# Power-line.net
KiCad netlist of a schematic drawn in Altium Designer
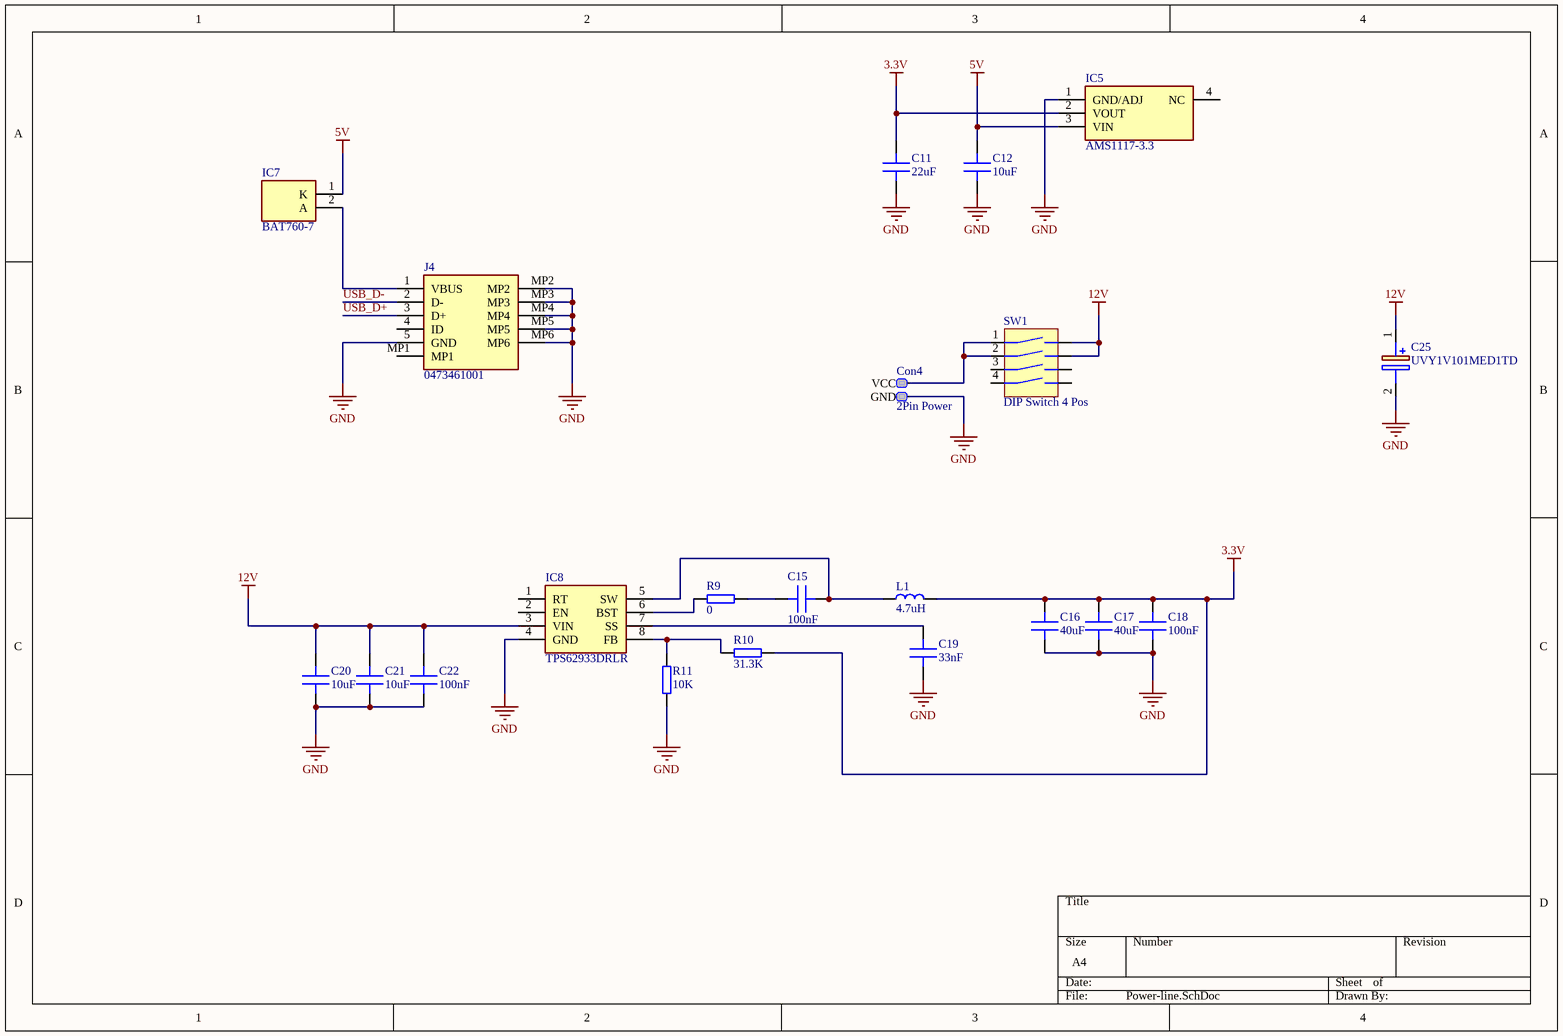
[diagram p0: Power-line.SchDoc]

(export (version "E")
  (design (tool "Eeschema 10.0.6"))
  (components
    (comp (ref "C11")
      (value "22uF")
      (footprint "C 0805")
      (description "MLCC Capacitor")
      (libsource (lib "Components") (part "Capacitor"))
    )
    (comp (ref "C12")
      (value "10uF")
      (footprint "C 0805")
      (description "MLCC Capacitor")
      (libsource (lib "Components") (part "Capacitor"))
    )
    (comp (ref "C15")
      (value "100nF")
      (footprint "C 0402")
      (description "MLCC Capacitor")
      (libsource (lib "Components") (part "Capacitor"))
    )
    (comp (ref "C16")
      (value "40uF")
      (footprint "C 1206")
      (description "MLCC Capacitor")
      (libsource (lib "Components") (part "Capacitor"))
    )
    (comp (ref "C17")
      (value "40uF")
      (footprint "C 1206")
      (description "MLCC Capacitor")
      (libsource (lib "Components") (part "Capacitor"))
    )
    (comp (ref "C18")
      (value "100nF")
      (footprint "C 0603")
      (description "MLCC Capacitor")
      (libsource (lib "Components") (part "Capacitor"))
    )
    (comp (ref "C19")
      (value "33nF")
      (footprint "C 0402")
      (description "MLCC Capacitor")
      (libsource (lib "Components") (part "Capacitor"))
    )
    (comp (ref "C20")
      (value "10uF")
      (footprint "C 1206")
      (description "MLCC Capacitor")
      (libsource (lib "Components") (part "Capacitor"))
    )
    (comp (ref "C21")
      (value "10uF")
      (footprint "C 1206")
      (description "MLCC Capacitor")
      (libsource (lib "Components") (part "Capacitor"))
    )
    (comp (ref "C22")
      (value "100nF")
      (footprint "C 0603")
      (description "MLCC Capacitor")
      (libsource (lib "Components") (part "Capacitor"))
    )
    (comp (ref "C25")
      (value "UVY1V101MED1TD")
      (footprint "SamacSys:CAPPRD250W50D655H1250")
      (description "Capacitor Polarised")
      (libsource (lib "lf_esp_sch_lib") (part "UVY1V101MED1TD"))
    )
    (comp (ref "Con4")
      (value "2Pin Power")
      (footprint "B2B-ZR-SM4A-TF")
      (libsource (lib "Connectors") (part "2Pin Power"))
    )
    (comp (ref "IC5")
      (value "AMS1117-3.3")
      (footprint "SamacSys:SOT229P700X180-4N")
      (description "Integrated Circuit")
      (libsource (lib "lf_esp_sch_lib") (part "AMS1117-3.3"))
    )
    (comp (ref "IC7")
      (value "BAT760-7")
      (footprint "SamacSys:SOD2513X120N")
      (description "Integrated Circuit")
      (libsource (lib "lf_esp_sch_lib") (part "BAT760-7"))
    )
    (comp (ref "IC8")
      (value "TPS62933DRLR")
      (footprint "SamacSys:SOTFL50P160X60-8N")
      (description "Integrated Circuit")
      (fields (field (name "MOUSER PART NUMBER") "595-TPS62933DRLR"))
      (libsource (lib "*") (part "TPS62933DRLR"))
    )
    (comp (ref "J4")
      (value "0473461001")
      (footprint "SamacSys:0473461001")
      (description "Connector")
      (libsource (lib "lf_esp_sch_lib") (part "0473461001"))
    )
    (comp (ref "L1")
      (value "4.7uH")
      (footprint "HPI0630")
      (description "General pourpouse inductor")
      (libsource (lib "Components") (part "Inductor"))
    )
    (comp (ref "R9")
      (value "0")
      (footprint "R 0402")
      (description "General pourpouse resistor")
      (libsource (lib "Components") (part "Resistor"))
    )
    (comp (ref "R10")
      (value "31.3K")
      (footprint "R 0402")
      (description "General pourpouse resistor")
      (libsource (lib "Components") (part "Resistor"))
    )
    (comp (ref "R11")
      (value "10K")
      (footprint "R 0402")
      (description "General pourpouse resistor")
      (libsource (lib "Components") (part "Resistor"))
    )
    (comp (ref "SW1")
      (value "DIP Switch 4 Pos")
      (footprint "DIP Switch 4 pos 2.54mm")
      (libsource (lib "Switches") (part "DIP Switch 4 Pos"))
    )
  )
  (nets
    (net (code "1") (name "/USB_D+") (class "Default")
      (node (ref "J4") (pin "3") (pinfunction "D+_3") (pintype "passive"))
    )
    (net (code "2") (name "/USB_D-") (class "Default")
      (node (ref "J4") (pin "2") (pinfunction "D-_2") (pintype "passive"))
    )
    (net (code "3") (name "3.3V") (class "Default")
      (node (ref "C11") (pin "1") (pinfunction "1_1") (pintype "passive"))
      (node (ref "C16") (pin "1") (pinfunction "1_1") (pintype "passive"))
      (node (ref "C17") (pin "1") (pinfunction "1_1") (pintype "passive"))
      (node (ref "C18") (pin "1") (pinfunction "1_1") (pintype "passive"))
      (node (ref "IC5") (pin "2") (pinfunction "VOUT_2") (pintype "passive"))
      (node (ref "L1") (pin "2") (pinfunction "2_2") (pintype "passive"))
      (node (ref "R10") (pin "1") (pinfunction "1_1") (pintype "passive"))
    )
    (net (code "4") (name "5V") (class "Default")
      (node (ref "C12") (pin "1") (pinfunction "1_1") (pintype "passive"))
      (node (ref "IC5") (pin "3") (pinfunction "VIN_3") (pintype "passive"))
      (node (ref "IC7") (pin "1") (pinfunction "K_1") (pintype "passive"))
    )
    (net (code "5") (name "12V") (class "Default")
      (node (ref "C20") (pin "1") (pinfunction "1_1") (pintype "passive"))
      (node (ref "C21") (pin "1") (pinfunction "1_1") (pintype "passive"))
      (node (ref "C22") (pin "1") (pinfunction "1_1") (pintype "passive"))
      (node (ref "C25") (pin "1") (pinfunction "+_1") (pintype "passive"))
      (node (ref "IC8") (pin "3") (pinfunction "VIN_3") (pintype "passive"))
      (node (ref "SW1") (pin "7") (pinfunction "7_7") (pintype "passive"))
      (node (ref "SW1") (pin "8") (pinfunction "8_8") (pintype "passive"))
    )
    (net (code "6") (name "GND") (class "Default")
      (node (ref "C11") (pin "2") (pinfunction "2_2") (pintype "passive"))
      (node (ref "C12") (pin "2") (pinfunction "2_2") (pintype "passive"))
      (node (ref "C16") (pin "2") (pinfunction "2_2") (pintype "passive"))
      (node (ref "C17") (pin "2") (pinfunction "2_2") (pintype "passive"))
      (node (ref "C18") (pin "2") (pinfunction "2_2") (pintype "passive"))
      (node (ref "C19") (pin "2") (pinfunction "2_2") (pintype "passive"))
      (node (ref "C20") (pin "2") (pinfunction "2_2") (pintype "passive"))
      (node (ref "C21") (pin "2") (pinfunction "2_2") (pintype "passive"))
      (node (ref "C22") (pin "2") (pinfunction "2_2") (pintype "passive"))
      (node (ref "C25") (pin "2") (pinfunction "-_2") (pintype "passive"))
      (node (ref "Con4") (pin "2") (pinfunction "GND_2") (pintype "passive"))
      (node (ref "IC5") (pin "1") (pinfunction "GND/ADJ_1") (pintype "passive"))
      (node (ref "IC8") (pin "4") (pinfunction "GND_4") (pintype "passive"))
      (node (ref "J4") (pin "5") (pinfunction "GND_5") (pintype "passive"))
      (node (ref "J4") (pin "MP2") (pinfunction "MP2_MP2") (pintype "passive"))
      (node (ref "J4") (pin "MP3") (pinfunction "MP3_MP3") (pintype "passive"))
      (node (ref "J4") (pin "MP4") (pinfunction "MP4_MP4") (pintype "passive"))
      (node (ref "J4") (pin "MP5") (pinfunction "MP5_MP5") (pintype "passive"))
      (node (ref "J4") (pin "MP6") (pinfunction "MP6_MP6") (pintype "passive"))
      (node (ref "R11") (pin "1") (pinfunction "1_1") (pintype "passive"))
    )
    (net (code "7") (name "Net-(C15-Pad1)") (class "Default")
      (node (ref "C15") (pin "1") (pinfunction "1_1") (pintype "passive"))
      (node (ref "R9") (pin "1") (pinfunction "1_1") (pintype "passive"))
    )
    (net (code "8") (name "Net-(Con4-VCC)") (class "Default")
      (node (ref "Con4") (pin "1") (pinfunction "VCC_1") (pintype "passive"))
      (node (ref "SW1") (pin "1") (pinfunction "1_1") (pintype "passive"))
      (node (ref "SW1") (pin "2") (pinfunction "2_2") (pintype "passive"))
    )
    (net (code "9") (name "Net-(IC7-A)") (class "Default")
      (node (ref "IC7") (pin "2") (pinfunction "A_2") (pintype "passive"))
      (node (ref "J4") (pin "1") (pinfunction "VBUS_1") (pintype "passive"))
    )
    (net (code "10") (name "Net-(IC8-BST)") (class "Default")
      (node (ref "IC8") (pin "6") (pinfunction "BST_6") (pintype "passive"))
      (node (ref "R9") (pin "2") (pinfunction "2_2") (pintype "passive"))
    )
    (net (code "11") (name "Net-(IC8-FB)") (class "Default")
      (node (ref "IC8") (pin "8") (pinfunction "FB_8") (pintype "passive"))
      (node (ref "R10") (pin "2") (pinfunction "2_2") (pintype "passive"))
      (node (ref "R11") (pin "2") (pinfunction "2_2") (pintype "passive"))
    )
    (net (code "12") (name "Net-(IC8-SS)") (class "Default")
      (node (ref "C19") (pin "1") (pinfunction "1_1") (pintype "passive"))
      (node (ref "IC8") (pin "7") (pinfunction "SS_7") (pintype "passive"))
    )
    (net (code "13") (name "Net-(IC8-SW)") (class "Default")
      (node (ref "C15") (pin "2") (pinfunction "2_2") (pintype "passive"))
      (node (ref "IC8") (pin "5") (pinfunction "SW_5") (pintype "passive"))
      (node (ref "L1") (pin "1") (pinfunction "1_1") (pintype "passive"))
    )
    (net (code "14") (name "unconnected-(IC5-NC-Pad4)") (class "Default")
      (node (ref "IC5") (pin "4") (pinfunction "NC_4") (pintype "passive"))
    )
    (net (code "15") (name "unconnected-(IC8-EN-Pad2)") (class "Default")
      (node (ref "IC8") (pin "2") (pinfunction "EN_2") (pintype "passive"))
    )
    (net (code "16") (name "unconnected-(IC8-RT-Pad1)") (class "Default")
      (node (ref "IC8") (pin "1") (pinfunction "RT_1") (pintype "passive"))
    )
    (net (code "17") (name "unconnected-(J4-ID-Pad4)") (class "Default")
      (node (ref "J4") (pin "4") (pinfunction "ID_4") (pintype "passive"))
    )
    (net (code "18") (name "unconnected-(J4-PadMP1)") (class "Default")
      (node (ref "J4") (pin "MP1") (pinfunction "MP1_MP1") (pintype "passive"))
    )
    (net (code "19") (name "unconnected-(SW1-Pad3)") (class "Default")
      (node (ref "SW1") (pin "3") (pinfunction "3_3") (pintype "passive"))
    )
    (net (code "20") (name "unconnected-(SW1-Pad4)") (class "Default")
      (node (ref "SW1") (pin "4") (pinfunction "4_4") (pintype "passive"))
    )
    (net (code "21") (name "unconnected-(SW1-Pad5)") (class "Default")
      (node (ref "SW1") (pin "5") (pinfunction "5_5") (pintype "passive"))
    )
    (net (code "22") (name "unconnected-(SW1-Pad6)") (class "Default")
      (node (ref "SW1") (pin "6") (pinfunction "6_6") (pintype "passive"))
    )
  )
)
